# Comparator.net
KiCad netlist of a schematic drawn in Altium Designer
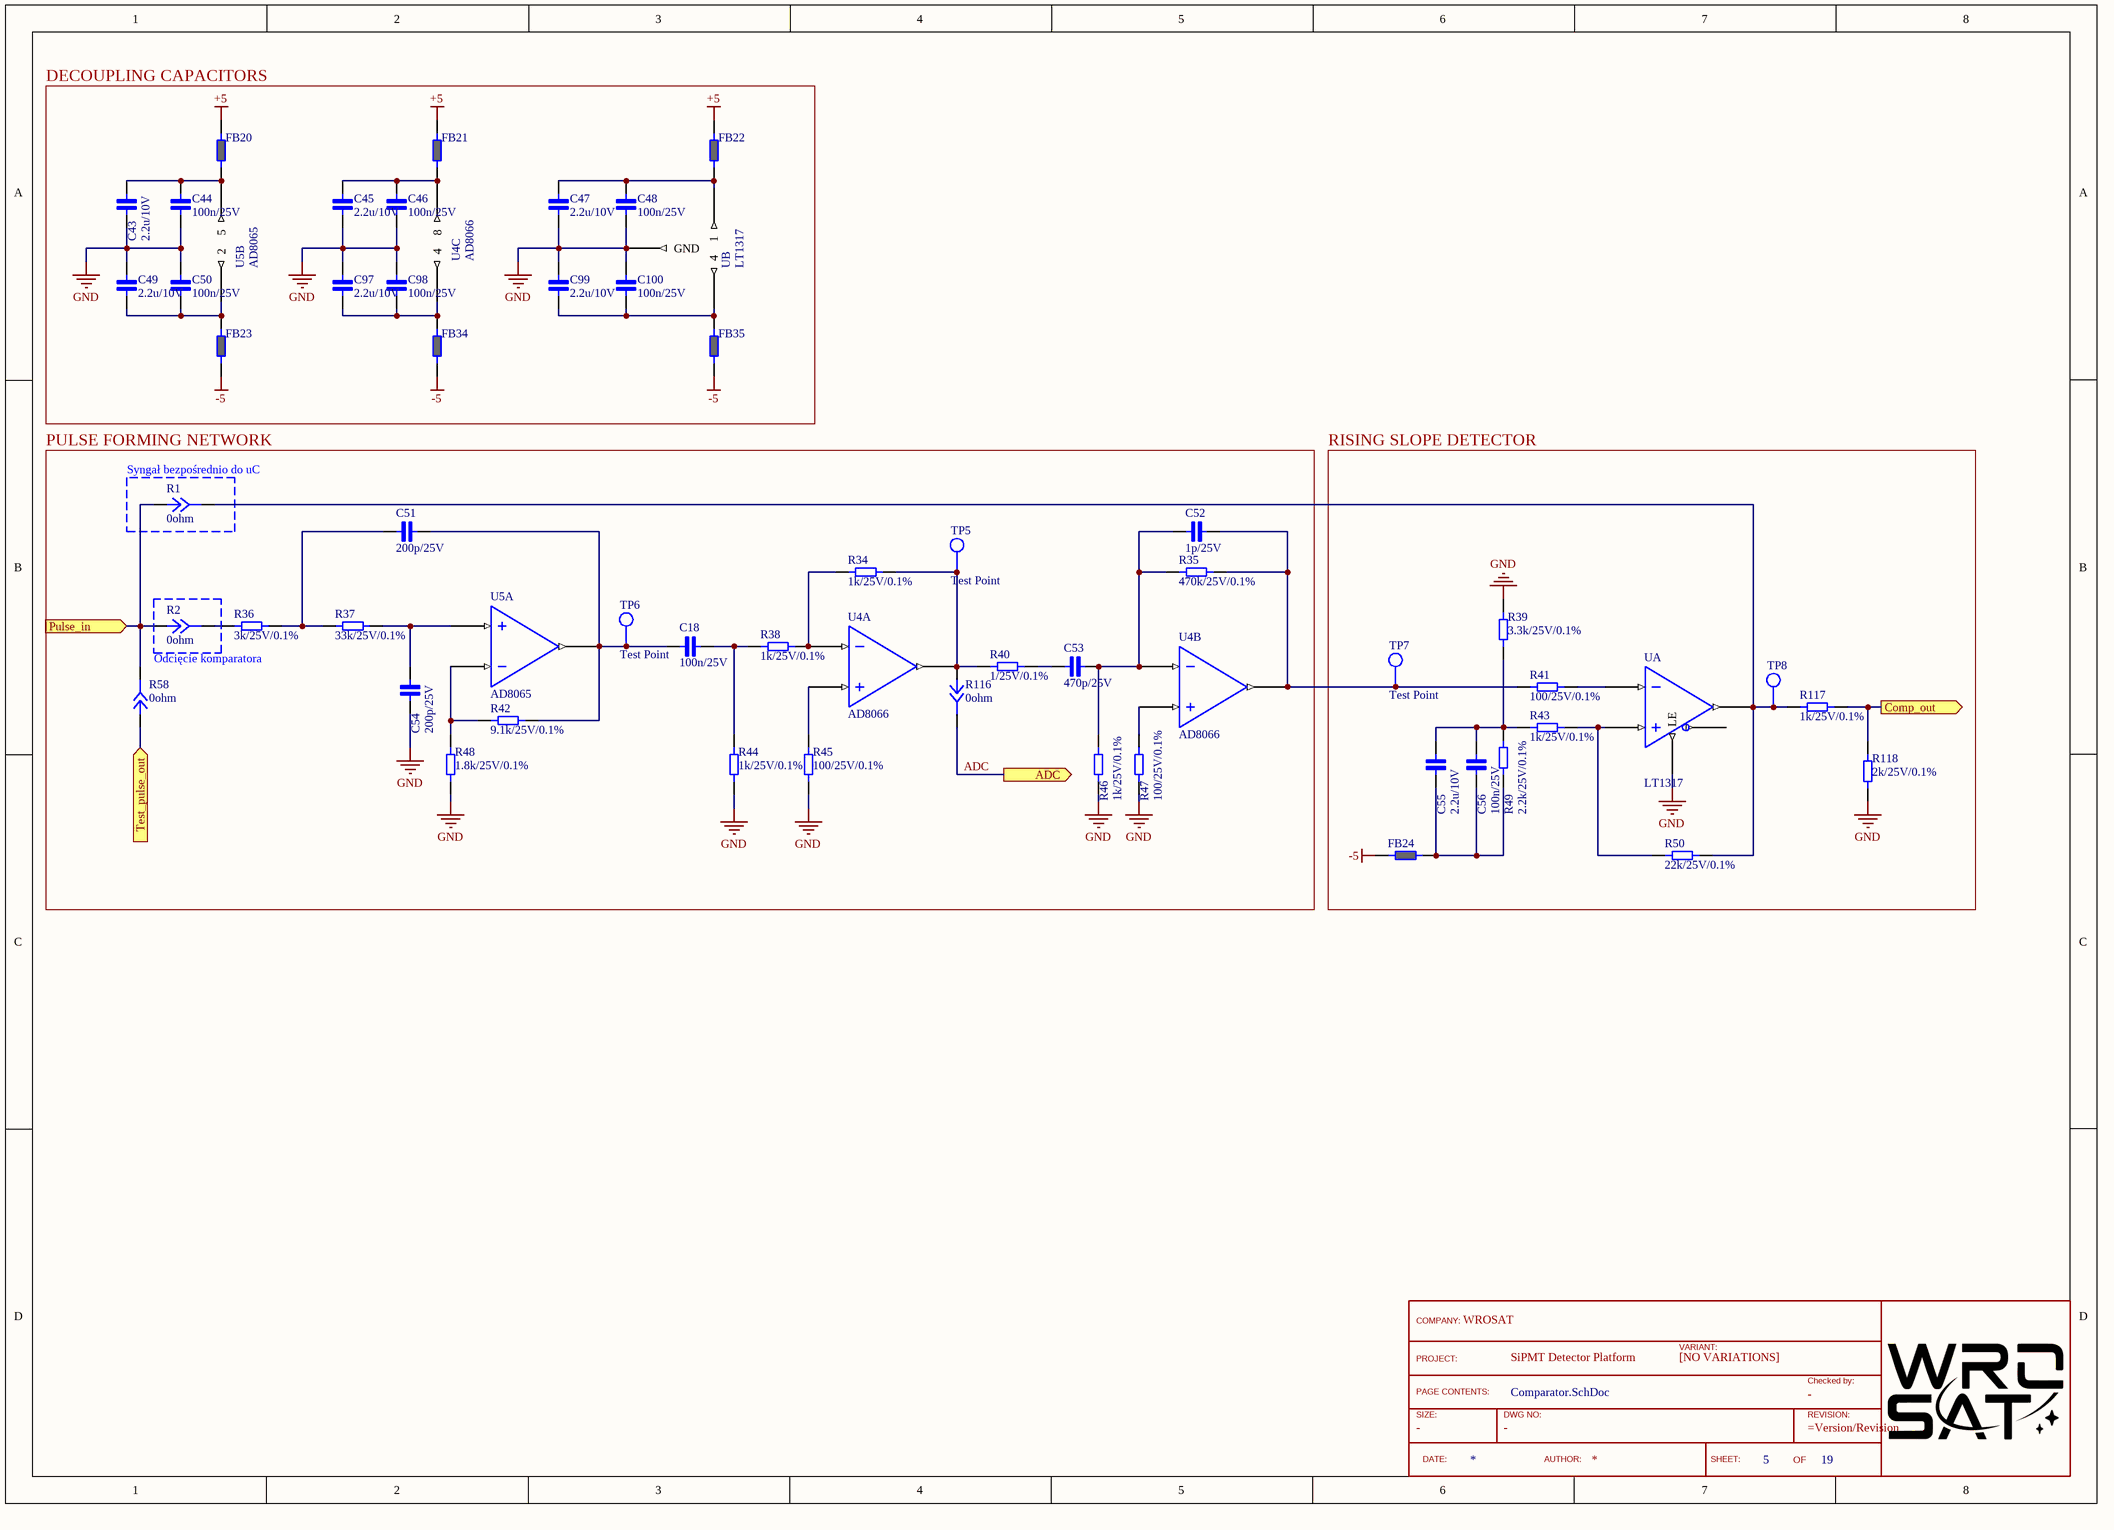
[diagram p0: Comparator.SchDoc]

(export (version "E")
  (design (tool "Eeschema 10.0.6"))
  (components
    (comp (ref "C18")
      (value "100n/25V")
      (footprint "Cap_0402")
      (description "Ceramic Capacitor 100n / 0402 / 25V / ±5%, Wurth Elektronik MLCC")
      (libsource (lib "Cubesat_lib") (part "Cap_0402_100n"))
    )
    (comp (ref "C43")
      (value "2.2u/10V")
      (footprint "Cap_0402")
      (description "Ceramic Capacitor 2.2uF / 0402 / 10V / ±5%, Wurth Elektronik MLCC")
      (libsource (lib "Cubesat_lib") (part "Cap_0402_2.2u"))
    )
    (comp (ref "C44")
      (value "100n/25V")
      (footprint "Cap_0402")
      (description "Ceramic Capacitor 100n / 0402 / 25V / ±5%, Wurth Elektronik MLCC")
      (libsource (lib "") (part "Cap_0402_100n_1"))
    )
    (comp (ref "C45")
      (value "2.2u/10V")
      (footprint "Cap_0402")
      (description "Ceramic Capacitor 2.2uF / 0402 / 10V / ±5%, Wurth Elektronik MLCC")
      (libsource (lib "Cubesat_lib") (part "Cap_0402_2.2u"))
    )
    (comp (ref "C46")
      (value "100n/25V")
      (footprint "Cap_0402")
      (description "Ceramic Capacitor 100n / 0402 / 25V / ±5%, Wurth Elektronik MLCC")
      (libsource (lib "") (part "Cap_0402_100n_1"))
    )
    (comp (ref "C47")
      (value "2.2u/10V")
      (footprint "Cap_0402")
      (description "Ceramic Capacitor 2.2uF / 0402 / 10V / ±5%, Wurth Elektronik MLCC")
      (libsource (lib "Cubesat_lib") (part "Cap_0402_2.2u"))
    )
    (comp (ref "C48")
      (value "100n/25V")
      (footprint "Cap_0402")
      (description "Ceramic Capacitor 100n / 0402 / 25V / ±5%, Wurth Elektronik MLCC")
      (libsource (lib "") (part "Cap_0402_100n_1"))
    )
    (comp (ref "C49")
      (value "2.2u/10V")
      (footprint "Cap_0402")
      (description "Ceramic Capacitor 2.2uF / 0402 / 10V / ±5%, Wurth Elektronik MLCC")
      (libsource (lib "Cubesat_lib") (part "Cap_0402_2.2u"))
    )
    (comp (ref "C50")
      (value "100n/25V")
      (footprint "Cap_0402")
      (description "Ceramic Capacitor 100n / 0402 / 25V / ±5%, Wurth Elektronik MLCC")
      (libsource (lib "") (part "Cap_0402_100n_1"))
    )
    (comp (ref "C51")
      (value "200p/25V")
      (footprint "Cap_0402")
      (description "0402 / 25V / ±5%, Wurth Elektronik MLCC")
      (libsource (lib "") (part "Cap_0402_200p_1"))
    )
    (comp (ref "C52")
      (value "1p/25V")
      (footprint "Cap_0402")
      (description "0402 / 25V / ±5%, Wurth Elektronik MLCC")
      (libsource (lib "Cubesat_lib") (part "Cap_0402_1p"))
    )
    (comp (ref "C53")
      (value "470p/25V")
      (footprint "Cap_0402")
      (description "0402 / 25V / ±5%, Wurth Elektronik MLCC")
      (libsource (lib "Cubesat_lib") (part "Cap_0402_470p"))
    )
    (comp (ref "C54")
      (value "200p/25V")
      (footprint "Cap_0402")
      (description "0402 / 25V / ±5%, Wurth Elektronik MLCC")
      (libsource (lib "Cubesat_lib") (part "Cap_0402_200p"))
    )
    (comp (ref "C55")
      (value "2.2u/10V")
      (footprint "Cap_0402")
      (description "Ceramic Capacitor 2.2uF / 0402 / 10V / ±5%, Wurth Elektronik MLCC")
      (libsource (lib "Cubesat_lib") (part "Cap_0402_2.2u"))
    )
    (comp (ref "C56")
      (value "100n/25V")
      (footprint "Cap_0402")
      (description "Ceramic Capacitor 100n / 0402 / 25V / ±5%, Wurth Elektronik MLCC")
      (libsource (lib "") (part "Cap_0402_100n_1"))
    )
    (comp (ref "C97")
      (value "2.2u/10V")
      (footprint "Cap_0402")
      (description "Ceramic Capacitor 2.2uF / 0402 / 10V / ±5%, Wurth Elektronik MLCC")
      (libsource (lib "Cubesat_lib") (part "Cap_0402_2.2u"))
    )
    (comp (ref "C98")
      (value "100n/25V")
      (footprint "Cap_0402")
      (description "Ceramic Capacitor 100n / 0402 / 25V / ±5%, Wurth Elektronik MLCC")
      (libsource (lib "") (part "Cap_0402_100n_1"))
    )
    (comp (ref "C99")
      (value "2.2u/10V")
      (footprint "Cap_0402")
      (description "Ceramic Capacitor 2.2uF / 0402 / 10V / ±5%, Wurth Elektronik MLCC")
      (libsource (lib "Cubesat_lib") (part "Cap_0402_2.2u"))
    )
    (comp (ref "C100")
      (value "100n/25V")
      (footprint "Cap_0402")
      (description "Ceramic Capacitor 100n / 0402 / 25V / ±5%, Wurth Elektronik MLCC")
      (libsource (lib "") (part "Cap_0402_100n_1"))
    )
    (comp (ref "FB20")
      (value "Ferrite_bead_0402")
      (footprint "FERRITE_0402")
      (description "Ferrite bead, wurth 74269241102")
      (libsource (lib "Cubesat_lib") (part "Ferrite_bead_0402"))
    )
    (comp (ref "FB21")
      (value "Ferrite_bead_0402")
      (footprint "FERRITE_0402")
      (description "Ferrite bead, wurth 74269241102")
      (libsource (lib "Cubesat_lib") (part "Ferrite_bead_0402"))
    )
    (comp (ref "FB22")
      (value "Ferrite_bead_0402")
      (footprint "FERRITE_0402")
      (description "Ferrite bead, wurth 74269241102")
      (libsource (lib "Cubesat_lib") (part "Ferrite_bead_0402"))
    )
    (comp (ref "FB23")
      (value "Ferrite_bead_0402")
      (footprint "FERRITE_0402")
      (description "Ferrite bead, wurth 74269241102")
      (libsource (lib "Cubesat_lib") (part "Ferrite_bead_0402"))
    )
    (comp (ref "FB24")
      (value "Ferrite_bead_0402")
      (footprint "FERRITE_0402")
      (description "Ferrite bead, wurth 74269241102")
      (libsource (lib "") (part "Ferrite_bead_0402_1"))
    )
    (comp (ref "FB34")
      (value "Ferrite_bead_0402")
      (footprint "FERRITE_0402")
      (description "Ferrite bead, wurth 74269241102")
      (libsource (lib "Cubesat_lib") (part "Ferrite_bead_0402"))
    )
    (comp (ref "FB35")
      (value "Ferrite_bead_0402")
      (footprint "FERRITE_0402")
      (description "Ferrite bead, wurth 74269241102")
      (libsource (lib "Cubesat_lib") (part "Ferrite_bead_0402"))
    )
    (comp (ref "R1") (value "0ohm") (footprint "Jumper 2") (libsource (lib "Cubesat_lib") (part "Jumper")))
    (comp (ref "R2") (value "0ohm") (footprint "Jumper 2") (libsource (lib "Cubesat_lib") (part "Jumper")))
    (comp (ref "R34")
      (value "1k/25V/0.1%")
      (footprint "RES_0402")
      (description "Vishay, thin film resistor 1k/25V/0.1%")
      (libsource (lib "") (part "Res_0402_1k_1"))
    )
    (comp (ref "R35")
      (value "470k/25V/0.1%")
      (footprint "RES_0402")
      (description "Vishay, thin film resistor 470k/25V/0.1%")
      (libsource (lib "Cubesat_lib") (part "Res_0402_470k"))
    )
    (comp (ref "R36")
      (value "3k/25V/0.1%")
      (footprint "RES_0402")
      (description "Vishay, thin film resistor 3k/25V/0.1%")
      (libsource (lib "Cubesat_lib") (part "Res_0402_3k"))
    )
    (comp (ref "R37")
      (value "33k/25V/0.1%")
      (footprint "RES_0402")
      (description "Vishay, thin film resistor 33k/25V/0.1%")
      (libsource (lib "Cubesat_lib") (part "Res_0402_33k"))
    )
    (comp (ref "R38")
      (value "1k/25V/0.1%")
      (footprint "RES_0402")
      (description "Vishay, thin film resistor 1k/25V/0.1%")
      (libsource (lib "") (part "Res_0402_1k_1"))
    )
    (comp (ref "R39")
      (value "3.3k/25V/0.1%")
      (footprint "RES_0402")
      (description "Vishay, thin film resistor 3.3k/25V/0.1%")
      (libsource (lib "Cubesat_lib") (part "Res_0402_3.3k"))
    )
    (comp (ref "R40")
      (value "1/25V/0.1%")
      (footprint "RES_0402")
      (description "Vishay, thin film resistor 1/25V/0.1%")
      (libsource (lib "Cubesat_lib") (part "Res_0402_1"))
    )
    (comp (ref "R41")
      (value "100/25V/0.1%")
      (footprint "RES_0402")
      (description "Vishay, thin film resistor 100/25V/0.1%")
      (libsource (lib "") (part "Res_0402_100_1"))
    )
    (comp (ref "R42")
      (value "9.1k/25V/0.1%")
      (footprint "RES_0402")
      (description "Vishay, thin film resistor 9.1k/25V/0.1%")
      (libsource (lib "Cubesat_lib") (part "Res_0402_9.1k"))
    )
    (comp (ref "R43")
      (value "1k/25V/0.1%")
      (footprint "RES_0402")
      (description "Vishay, thin film resistor 1k/25V/0.1%")
      (libsource (lib "") (part "Res_0402_1k_2"))
    )
    (comp (ref "R44")
      (value "1k/25V/0.1%")
      (footprint "RES_0402")
      (description "Vishay, thin film resistor 1k/25V/0.1%")
      (libsource (lib "") (part "Res_0402_1k_3"))
    )
    (comp (ref "R45")
      (value "100/25V/0.1%")
      (footprint "RES_0402")
      (description "Vishay, thin film resistor 100/25V/0.1%")
      (libsource (lib "Cubesat_lib") (part "Res_0402_100"))
    )
    (comp (ref "R46")
      (value "1k/25V/0.1%")
      (footprint "RES_0402")
      (description "Vishay, thin film resistor 1k/25V/0.1%")
      (libsource (lib "Cubesat_lib") (part "Res_0402_1k"))
    )
    (comp (ref "R47")
      (value "100/25V/0.1%")
      (footprint "RES_0402")
      (description "Vishay, thin film resistor 100/25V/0.1%")
      (libsource (lib "Cubesat_lib") (part "Res_0402_100"))
    )
    (comp (ref "R48")
      (value "1.8k/25V/0.1%")
      (footprint "RES_0402")
      (description "Vishay, thin film resistor 1.8k/25V/0.1%")
      (libsource (lib "Cubesat_lib") (part "Res_0402_1.8k"))
    )
    (comp (ref "R49")
      (value "2.2k/25V/0.1%")
      (footprint "RES_0402")
      (description "Vishay, thin film resistor 2.2k/25V/0.1%")
      (libsource (lib "Cubesat_lib") (part "Res_0402_2.2k"))
    )
    (comp (ref "R50")
      (value "22k/25V/0.1%")
      (footprint "RES_0402")
      (description "Vishay, thin film resistor 20k/25V/0.1%")
      (libsource (lib "Cubesat_lib") (part "Res_0402_22k"))
    )
    (comp (ref "R58") (value "0ohm") (footprint "Jumper 2") (libsource (lib "Cubesat_lib") (part "Jumper")))
    (comp (ref "R116") (value "0ohm") (footprint "Jumper 2") (libsource (lib "Cubesat_lib") (part "Jumper")))
    (comp (ref "R117")
      (value "1k/25V/0.1%")
      (footprint "RES_0402")
      (description "Vishay, thin film resistor 1k/25V/0.1%")
      (libsource (lib "") (part "Res_0402_1k_2"))
    )
    (comp (ref "R118")
      (value "2k/25V/0.1%")
      (footprint "RES_0402")
      (description "Vishay, thin film resistor 1k/25V/0.1%")
      (libsource (lib "") (part "Res_0402_1k_3"))
    )
    (comp (ref "TP5")
      (value "Test Point")
      (footprint "Test Point SMT")
      (libsource (lib "Cubesat_lib") (part "Test Point"))
    )
    (comp (ref "TP6")
      (value "Test Point")
      (footprint "Test Point SMT")
      (libsource (lib "Cubesat_lib") (part "Test Point"))
    )
    (comp (ref "TP7")
      (value "Test Point")
      (footprint "Test Point SMT")
      (libsource (lib "Cubesat_lib") (part "Test Point"))
    )
    (comp (ref "TP8")
      (value "Test Point")
      (footprint "Test Point SMT")
      (libsource (lib "Cubesat_lib") (part "Test Point"))
    )
    (comp (ref "U")
      (value "LT1317")
      (footprint "MSOP-8")
      (description "Single, 7ns, Low Power,\r\n3V/5V/±5V Rail-to-Rail Comparators")
      (libsource (lib "Cubesat_lib") (part "LT1317"))
    )
    (comp (ref "U4")
      (value "AD8066")
      (footprint "SOIC8")
      (description "High Performance, 145 MHz\r\nFastFET Op Amps")
      (libsource (lib "Cubesat_lib") (part "AD8066"))
    )
    (comp (ref "U5")
      (value "AD8065")
      (footprint "SOT-23-5")
      (description "High Performance, 145 MHz\r\nFastFET Op Amps")
      (libsource (lib "Cubesat_lib") (part "AD8065"))
    )
  )
  (nets
    (net (code "1") (name "+5") (class "Default")
      (node (ref "FB20") (pin "2") (pinfunction "2_2") (pintype "passive"))
      (node (ref "FB21") (pin "2") (pinfunction "2_2") (pintype "passive"))
      (node (ref "FB22") (pin "2") (pinfunction "2_2") (pintype "passive"))
    )
    (net (code "2") (name "-5") (class "Default")
      (node (ref "FB23") (pin "1") (pinfunction "1_1") (pintype "passive"))
      (node (ref "FB24") (pin "1") (pinfunction "1_1") (pintype "passive"))
      (node (ref "FB34") (pin "1") (pinfunction "1_1") (pintype "passive"))
      (node (ref "FB35") (pin "1") (pinfunction "1_1") (pintype "passive"))
    )
    (net (code "3") (name "/ADC") (class "Default")
      (node (ref "R116") (pin "2") (pinfunction "2_2") (pintype "passive"))
    )
    (net (code "4") (name "/Comp_out") (class "Default")
      (node (ref "R117") (pin "2") (pinfunction "2_2") (pintype "passive"))
      (node (ref "R118") (pin "2") (pinfunction "2_2") (pintype "passive"))
    )
    (net (code "5") (name "/Pulse_in") (class "Default")
      (node (ref "R1") (pin "1") (pinfunction "1_1") (pintype "passive"))
      (node (ref "R2") (pin "1") (pinfunction "1_1") (pintype "passive"))
      (node (ref "R58") (pin "2") (pinfunction "2_2") (pintype "passive"))
    )
    (net (code "6") (name "/Test_pulse_out") (class "Default")
      (node (ref "R58") (pin "1") (pinfunction "1_1") (pintype "passive"))
    )
    (net (code "7") (name "GND") (class "Default")
      (node (ref "C100") (pin "2") (pinfunction "2_2") (pintype "passive"))
      (node (ref "C43") (pin "1") (pinfunction "1_1") (pintype "passive"))
      (node (ref "C44") (pin "1") (pinfunction "1_1") (pintype "passive"))
      (node (ref "C45") (pin "1") (pinfunction "1_1") (pintype "passive"))
      (node (ref "C46") (pin "1") (pinfunction "1_1") (pintype "passive"))
      (node (ref "C47") (pin "1") (pinfunction "1_1") (pintype "passive"))
      (node (ref "C48") (pin "1") (pinfunction "1_1") (pintype "passive"))
      (node (ref "C49") (pin "2") (pinfunction "2_2") (pintype "passive"))
      (node (ref "C50") (pin "2") (pinfunction "2_2") (pintype "passive"))
      (node (ref "C54") (pin "1") (pinfunction "1_1") (pintype "passive"))
      (node (ref "C97") (pin "2") (pinfunction "2_2") (pintype "passive"))
      (node (ref "C98") (pin "2") (pinfunction "2_2") (pintype "passive"))
      (node (ref "C99") (pin "2") (pinfunction "2_2") (pintype "passive"))
      (node (ref "R118") (pin "1") (pinfunction "1_1") (pintype "passive"))
      (node (ref "R39") (pin "2") (pinfunction "2_2") (pintype "passive"))
      (node (ref "R44") (pin "1") (pinfunction "1_1") (pintype "passive"))
      (node (ref "R45") (pin "1") (pinfunction "1_1") (pintype "passive"))
      (node (ref "R46") (pin "2") (pinfunction "2_2") (pintype "passive"))
      (node (ref "R47") (pin "1") (pinfunction "1_1") (pintype "passive"))
      (node (ref "R48") (pin "1") (pinfunction "1_1") (pintype "passive"))
      (node (ref "U") (pin "5") (pinfunction "LE_5") (pintype "output"))
      (node (ref "U") (pin "6") (pinfunction "GND_6") (pintype "output"))
    )
    (net (code "8") (name "Net-(C18-Pad1)") (class "Default")
      (node (ref "C18") (pin "1") (pinfunction "1_1") (pintype "passive"))
      (node (ref "C51") (pin "2") (pinfunction "2_2") (pintype "passive"))
      (node (ref "R42") (pin "2") (pinfunction "2_2") (pintype "passive"))
      (node (ref "TP6") (pin "1") (pinfunction "1_1") (pintype "passive"))
      (node (ref "U5") (pin "1") (pinfunction "1_1") (pintype "output"))
    )
    (net (code "9") (name "Net-(C18-Pad2)") (class "Default")
      (node (ref "C18") (pin "2") (pinfunction "2_2") (pintype "passive"))
      (node (ref "R38") (pin "2") (pinfunction "2_2") (pintype "passive"))
      (node (ref "R44") (pin "2") (pinfunction "2_2") (pintype "passive"))
    )
    (net (code "10") (name "Net-(C43-Pad2)") (class "Default")
      (node (ref "C43") (pin "2") (pinfunction "2_2") (pintype "passive"))
      (node (ref "C44") (pin "2") (pinfunction "2_2") (pintype "passive"))
      (node (ref "FB20") (pin "1") (pinfunction "1_1") (pintype "passive"))
      (node (ref "U5") (pin "5") (pinfunction "5_5") (pintype "output"))
    )
    (net (code "11") (name "Net-(C45-Pad2)") (class "Default")
      (node (ref "C45") (pin "2") (pinfunction "2_2") (pintype "passive"))
      (node (ref "C46") (pin "2") (pinfunction "2_2") (pintype "passive"))
      (node (ref "FB21") (pin "1") (pinfunction "1_1") (pintype "passive"))
      (node (ref "U4") (pin "8") (pinfunction "8_8") (pintype "output"))
    )
    (net (code "12") (name "Net-(C47-Pad2)") (class "Default")
      (node (ref "C47") (pin "2") (pinfunction "2_2") (pintype "passive"))
      (node (ref "C48") (pin "2") (pinfunction "2_2") (pintype "passive"))
      (node (ref "FB22") (pin "1") (pinfunction "1_1") (pintype "passive"))
      (node (ref "U") (pin "1") (pinfunction "1_1") (pintype "output"))
    )
    (net (code "13") (name "Net-(C49-Pad1)") (class "Default")
      (node (ref "C49") (pin "1") (pinfunction "1_1") (pintype "passive"))
      (node (ref "C50") (pin "1") (pinfunction "1_1") (pintype "passive"))
      (node (ref "FB23") (pin "2") (pinfunction "2_2") (pintype "passive"))
      (node (ref "U5") (pin "2") (pinfunction "2_2") (pintype "output"))
    )
    (net (code "14") (name "Net-(C51-Pad1)") (class "Default")
      (node (ref "C51") (pin "1") (pinfunction "1_1") (pintype "passive"))
      (node (ref "R36") (pin "2") (pinfunction "2_2") (pintype "passive"))
      (node (ref "R37") (pin "1") (pinfunction "1_1") (pintype "passive"))
    )
    (net (code "15") (name "Net-(C52-Pad1)") (class "Default")
      (node (ref "C52") (pin "1") (pinfunction "1_1") (pintype "passive"))
      (node (ref "C53") (pin "2") (pinfunction "2_2") (pintype "passive"))
      (node (ref "R35") (pin "2") (pinfunction "2_2") (pintype "passive"))
      (node (ref "R46") (pin "1") (pinfunction "1_1") (pintype "passive"))
      (node (ref "U4") (pin "6") (pinfunction "6_6") (pintype "input"))
    )
    (net (code "16") (name "Net-(C52-Pad2)") (class "Default")
      (node (ref "C52") (pin "2") (pinfunction "2_2") (pintype "passive"))
      (node (ref "R35") (pin "1") (pinfunction "1_1") (pintype "passive"))
      (node (ref "R41") (pin "1") (pinfunction "1_1") (pintype "passive"))
      (node (ref "TP7") (pin "1") (pinfunction "1_1") (pintype "passive"))
      (node (ref "U4") (pin "7") (pinfunction "7_7") (pintype "output"))
    )
    (net (code "17") (name "Net-(C53-Pad1)") (class "Default")
      (node (ref "C53") (pin "1") (pinfunction "1_1") (pintype "passive"))
      (node (ref "R40") (pin "2") (pinfunction "2_2") (pintype "passive"))
    )
    (net (code "18") (name "Net-(C54-Pad2)") (class "Default")
      (node (ref "C54") (pin "2") (pinfunction "2_2") (pintype "passive"))
      (node (ref "R37") (pin "2") (pinfunction "2_2") (pintype "passive"))
      (node (ref "U5") (pin "3") (pinfunction "3_3") (pintype "input"))
    )
    (net (code "19") (name "Net-(C55-Pad1)") (class "Default")
      (node (ref "C55") (pin "1") (pinfunction "1_1") (pintype "passive"))
      (node (ref "C56") (pin "1") (pinfunction "1_1") (pintype "passive"))
      (node (ref "FB24") (pin "2") (pinfunction "2_2") (pintype "passive"))
      (node (ref "R49") (pin "1") (pinfunction "1_1") (pintype "passive"))
    )
    (net (code "20") (name "Net-(C55-Pad2)") (class "Default")
      (node (ref "C55") (pin "2") (pinfunction "2_2") (pintype "passive"))
      (node (ref "C56") (pin "2") (pinfunction "2_2") (pintype "passive"))
      (node (ref "R39") (pin "1") (pinfunction "1_1") (pintype "passive"))
      (node (ref "R43") (pin "1") (pinfunction "1_1") (pintype "passive"))
      (node (ref "R49") (pin "2") (pinfunction "2_2") (pintype "passive"))
    )
    (net (code "21") (name "Net-(C97-Pad1)") (class "Default")
      (node (ref "C97") (pin "1") (pinfunction "1_1") (pintype "passive"))
      (node (ref "C98") (pin "1") (pinfunction "1_1") (pintype "passive"))
      (node (ref "FB34") (pin "2") (pinfunction "2_2") (pintype "passive"))
      (node (ref "U4") (pin "4") (pinfunction "4_4") (pintype "output"))
    )
    (net (code "22") (name "Net-(C100-Pad1)") (class "Default")
      (node (ref "C100") (pin "1") (pinfunction "1_1") (pintype "passive"))
      (node (ref "C99") (pin "1") (pinfunction "1_1") (pintype "passive"))
      (node (ref "FB35") (pin "2") (pinfunction "2_2") (pintype "passive"))
      (node (ref "U") (pin "4") (pinfunction "4_4") (pintype "output"))
    )
    (net (code "23") (name "Net-(R1-Pad2)") (class "Default")
      (node (ref "R1") (pin "2") (pinfunction "2_2") (pintype "passive"))
      (node (ref "R117") (pin "1") (pinfunction "1_1") (pintype "passive"))
      (node (ref "R50") (pin "2") (pinfunction "2_2") (pintype "passive"))
      (node (ref "TP8") (pin "1") (pinfunction "1_1") (pintype "passive"))
      (node (ref "U") (pin "7") (pinfunction "7_7") (pintype "output"))
    )
    (net (code "24") (name "Net-(R2-Pad2)") (class "Default")
      (node (ref "R2") (pin "2") (pinfunction "2_2") (pintype "passive"))
      (node (ref "R36") (pin "1") (pinfunction "1_1") (pintype "passive"))
    )
    (net (code "25") (name "Net-(R41-Pad2)") (class "Default")
      (node (ref "R41") (pin "2") (pinfunction "2_2") (pintype "passive"))
      (node (ref "U") (pin "3") (pinfunction "3_3") (pintype "input"))
    )
    (net (code "26") (name "Net-(R42-Pad1)") (class "Default")
      (node (ref "R42") (pin "1") (pinfunction "1_1") (pintype "passive"))
      (node (ref "R48") (pin "2") (pinfunction "2_2") (pintype "passive"))
      (node (ref "U5") (pin "4") (pinfunction "4_4") (pintype "input"))
    )
    (net (code "27") (name "Net-(R43-Pad2)") (class "Default")
      (node (ref "R43") (pin "2") (pinfunction "2_2") (pintype "passive"))
      (node (ref "R50") (pin "1") (pinfunction "1_1") (pintype "passive"))
      (node (ref "U") (pin "2") (pinfunction "2_2") (pintype "input"))
    )
    (net (code "28") (name "Net-(R45-Pad2)") (class "Default")
      (node (ref "R45") (pin "2") (pinfunction "2_2") (pintype "passive"))
      (node (ref "U4") (pin "3") (pinfunction "3_3") (pintype "input"))
    )
    (net (code "29") (name "Net-(R47-Pad2)") (class "Default")
      (node (ref "R47") (pin "2") (pinfunction "2_2") (pintype "passive"))
      (node (ref "U4") (pin "5") (pinfunction "5_5") (pintype "input"))
    )
    (net (code "30") (name "Net-(R116-Pad1)") (class "Default")
      (node (ref "R116") (pin "1") (pinfunction "1_1") (pintype "passive"))
      (node (ref "R34") (pin "1") (pinfunction "1_1") (pintype "passive"))
      (node (ref "R40") (pin "1") (pinfunction "1_1") (pintype "passive"))
      (node (ref "TP5") (pin "1") (pinfunction "1_1") (pintype "passive"))
      (node (ref "U4") (pin "1") (pinfunction "1_1") (pintype "output"))
    )
    (net (code "31") (name "Net-(U4A-0)") (class "Default")
      (node (ref "R34") (pin "2") (pinfunction "2_2") (pintype "passive"))
      (node (ref "R38") (pin "1") (pinfunction "1_1") (pintype "passive"))
      (node (ref "U4") (pin "2") (pinfunction "0_2") (pintype "input"))
    )
    (net (code "32") (name "unconnected-(U-Pad8)") (class "Default")
      (node (ref "U") (pin "8") (pinfunction "8_8") (pintype "output"))
    )
  )
)
